# Sheet_3.net
KiCad netlist of a schematic drawn in Altium Designer
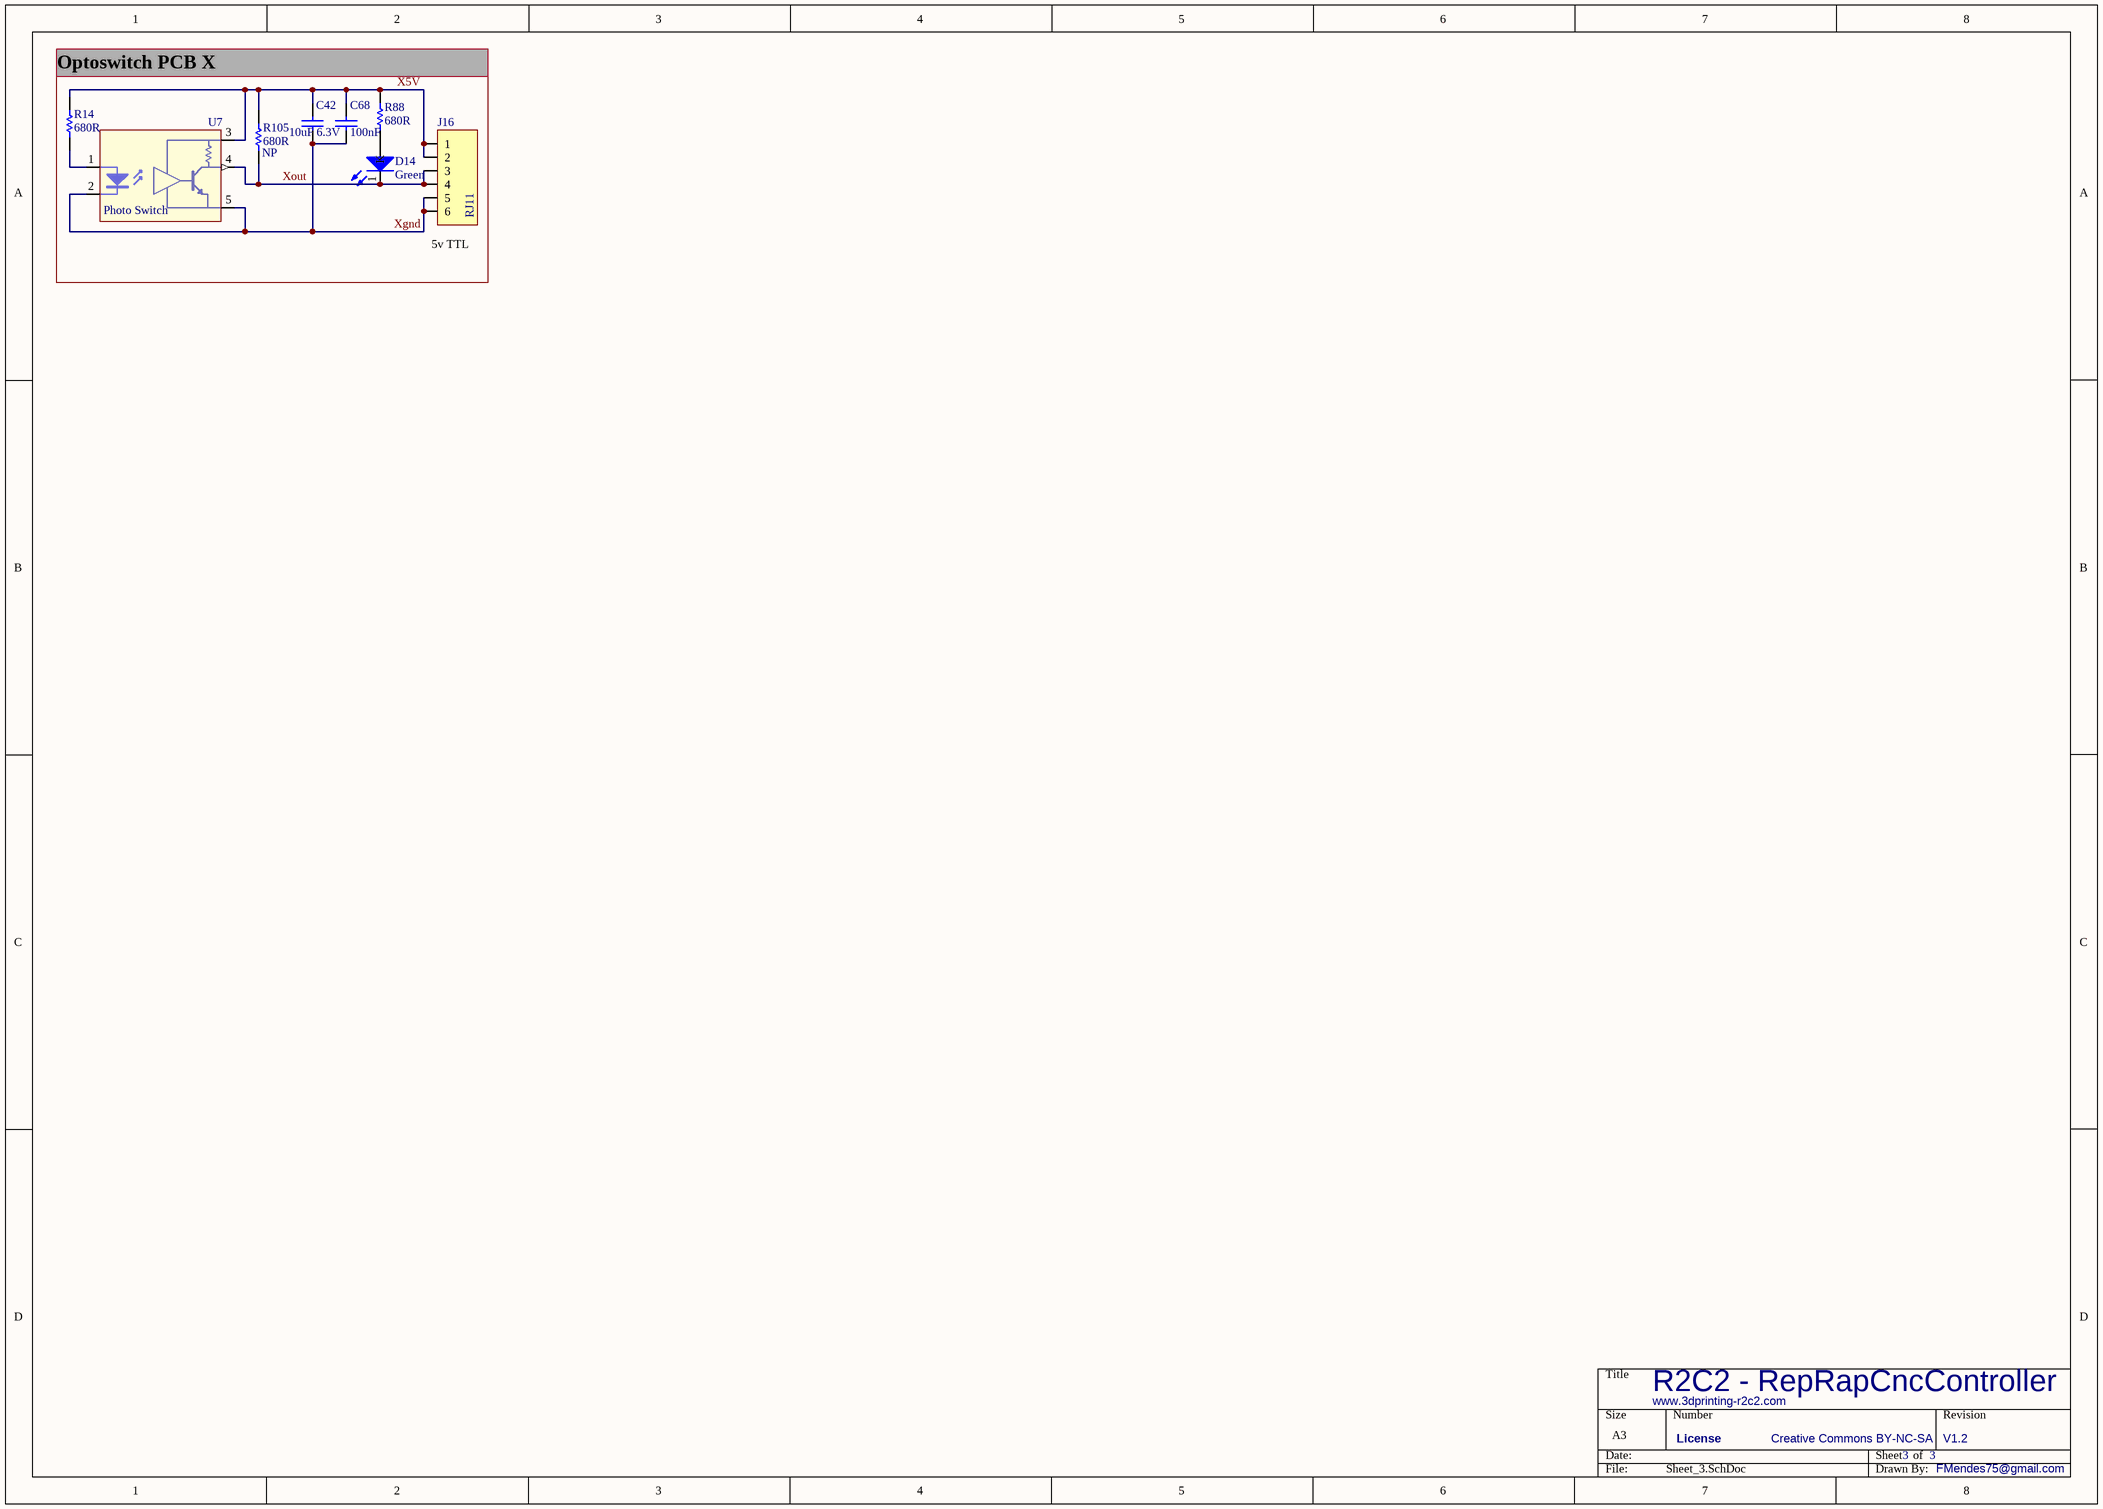
[diagram p0: Sheet_3.SchDoc]

(export (version "E")
  (design (tool "Eeschema 10.0.6"))
  (components
    (comp (ref "C42")
      (value "10uF 6.3V")
      (footprint "CAPC2012M")
      (description "Capacitor - MLCC; 0805; Y5V; 10UF; 6.3V")
      (fields (field (name "PART NUMBER") "10000001") (field (name "MANUFACTURER") "MULTICOMP"))
      (libsource (lib "HB_DB_Components") (part "Cap Non Pol"))
    )
    (comp (ref "C68")
      (value "100nF")
      (footprint "CAPC1608M")
      (description "Capacitor - MLCC; 0603; NP0; 50V")
      (fields (field (name "PART NUMBER") "10000054") (field (name "MANUFACTURER") "Multicomp"))
      (libsource (lib "HB_DB_Components") (part "Cap Non Pol"))
    )
    (comp (ref "D14")
      (value "Green")
      (footprint "LEDM_3216X12M")
      (description "Led - 1206; Green OSRAM")
      (fields (field (name "PART NUMBER") "10000008") (field (name "MANUFACTURER") "OSRAM"))
      (libsource (lib "HB_DB_Components") (part "LED"))
    )
    (comp (ref "J16")
      (value "RJ11")
      (footprint "MOLEX_95022-2667")
      (description "Connector - PCB; RJ11; 6/4 Low Profile; Hor.")
      (fields (field (name "PART NUMBER") "10000062") (field (name "MANUFACTURER") "Molex"))
      (libsource (lib "HB_DB_Components") (part "Con 6"))
    )
    (comp (ref "R14")
      (value "680R")
      (footprint "RESC1608M")
      (description "Resistor - 0603; 0.063W; 1%")
      (fields (field (name "PART NUMBER") "10000061") (field (name "MANUFACTURER") "Multicomp"))
      (libsource (lib "HB_DB_Components") (part "Res"))
    )
    (comp (ref "R88")
      (value "680R")
      (footprint "RESC1608M")
      (description "Resistor - 0603; 0.063W; 1%")
      (fields (field (name "PART NUMBER") "10000061") (field (name "MANUFACTURER") "Multicomp"))
      (libsource (lib "HB_DB_Components") (part "Res"))
    )
    (comp (ref "R105")
      (value "680R")
      (footprint "RESC1608M")
      (description "Resistor - 0603; 0.063W; 1%")
      (fields
        (field (name "PART NUMBER") "10000061")
        (field (name "MANUFACTURER") "Multicomp")
        (field (name "POPULATE") "NP")
      )
      (libsource (lib "HB_DB_Components") (part "Res"))
    )
    (comp (ref "U7")
      (value "Photo Switch")
      (footprint "OPIC_122x50x10")
      (description "Opto - Switch; OPIC Sharp; Slotted 3mm; Vcc 5v")
      (fields (field (name "PART NUMBER") "10000075") (field (name "MANUFACTURER") "Sharp"))
      (libsource (lib "HB_DB_Components") (part "Photo_Switch"))
    )
  )
  (nets
    (net (code "1") (name "/X5V") (class "Default")
      (node (ref "C42") (pin "2") (pinfunction "2_2") (pintype "passive"))
      (node (ref "C68") (pin "2") (pinfunction "2_2") (pintype "passive"))
      (node (ref "J16") (pin "1") (pinfunction "1_1") (pintype "passive"))
      (node (ref "J16") (pin "2") (pinfunction "2_2") (pintype "passive"))
      (node (ref "R105") (pin "2") (pinfunction "2_2") (pintype "passive"))
      (node (ref "R14") (pin "2") (pinfunction "2_2") (pintype "passive"))
      (node (ref "R88") (pin "2") (pinfunction "2_2") (pintype "passive"))
      (node (ref "U7") (pin "3") (pinfunction "Vcc_3") (pintype "power_in"))
    )
    (net (code "2") (name "/Xgnd") (class "Default")
      (node (ref "C42") (pin "1") (pinfunction "1_1") (pintype "passive"))
      (node (ref "C68") (pin "1") (pinfunction "1_1") (pintype "passive"))
      (node (ref "J16") (pin "5") (pinfunction "5_5") (pintype "passive"))
      (node (ref "J16") (pin "6") (pinfunction "6_6") (pintype "passive"))
      (node (ref "U7") (pin "2") (pinfunction "K_2") (pintype "passive"))
      (node (ref "U7") (pin "5") (pinfunction "GND_5") (pintype "power_in"))
    )
    (net (code "3") (name "/Xout") (class "Default")
      (node (ref "D14") (pin "1") (pinfunction "K_1") (pintype "passive"))
      (node (ref "J16") (pin "3") (pinfunction "3_3") (pintype "passive"))
      (node (ref "J16") (pin "4") (pinfunction "4_4") (pintype "passive"))
      (node (ref "R105") (pin "1") (pinfunction "1_1") (pintype "passive"))
      (node (ref "U7") (pin "4") (pinfunction "Out_4") (pintype "output"))
    )
    (net (code "4") (name "Net-(D14-A)") (class "Default")
      (node (ref "D14") (pin "2") (pinfunction "A_2") (pintype "passive"))
      (node (ref "R88") (pin "1") (pinfunction "1_1") (pintype "passive"))
    )
    (net (code "5") (name "Net-(U7-A)") (class "Default")
      (node (ref "R14") (pin "1") (pinfunction "1_1") (pintype "passive"))
      (node (ref "U7") (pin "1") (pinfunction "A_1") (pintype "passive"))
    )
  )
)
